# k02-breakout.net
KiCad netlist of a schematic drawn in Altium Designer
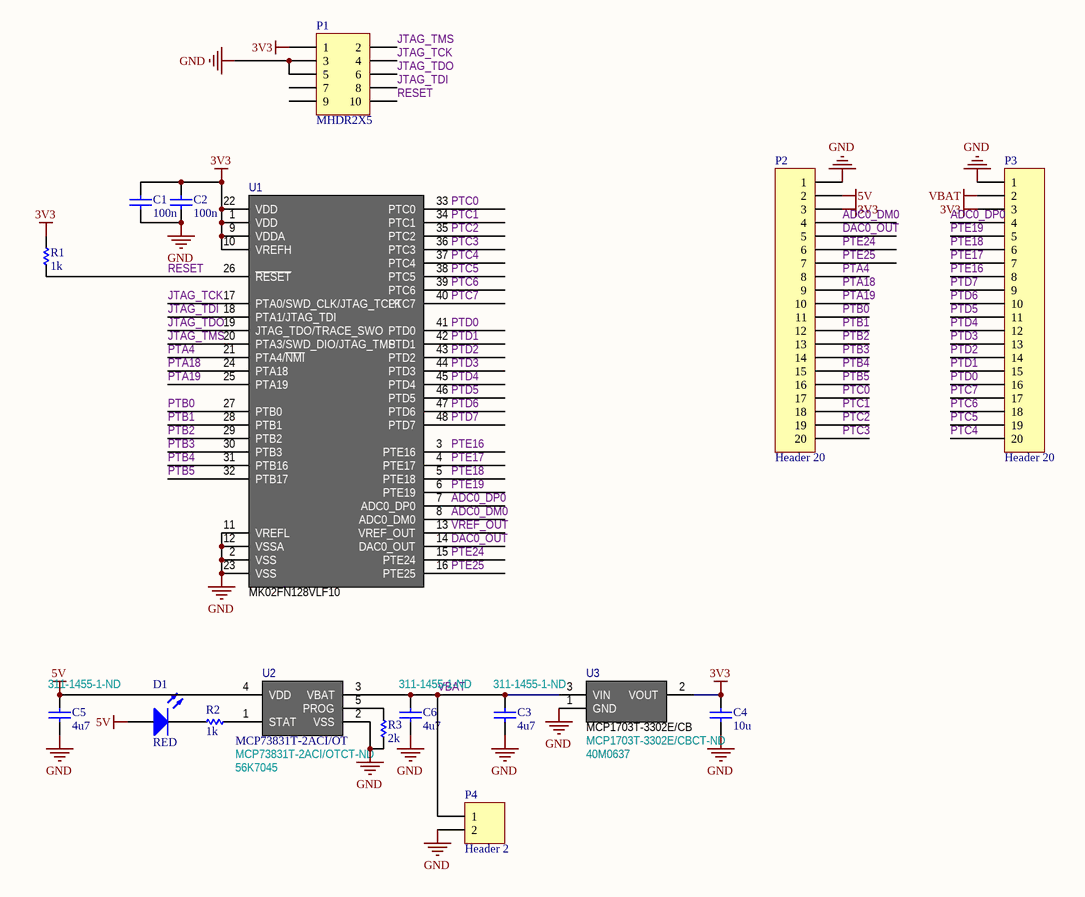
[diagram p0: k02-breakout.SchDoc]

(export (version "E")
  (design (tool "Eeschema 10.0.6"))
  (components
    (comp (ref "C1")
      (value "100n")
      (footprint "CAPC1608N")
      (description "Capacitor (Semiconductor SIM Model)")
      (fields (field (name "PUBLISHER") "Altium Limited"))
      (libsource (lib "Miscellaneous Devices") (part "Cap Semi"))
    )
    (comp (ref "C2")
      (value "100n")
      (footprint "CAPC1608N")
      (description "Capacitor (Semiconductor SIM Model)")
      (fields (field (name "PUBLISHER") "Altium Limited"))
      (libsource (lib "Miscellaneous Devices") (part "Cap Semi"))
    )
    (comp (ref "C3")
      (value "4u7")
      (footprint "CAPC1608N")
      (description "CAP SEMI 4U7 10V 0603")
      (fields
        (field (name "SUPPLIER PART NUMBER 1") "311-1455-1-ND")
        (field (name "PUBLISHER") "Altium Limited")
      )
      (libsource (lib "Miscellaneous Devices") (part "Cap Semi"))
    )
    (comp (ref "C4")
      (value "10u")
      (footprint "CAPC1608N")
      (description "Capacitor (Semiconductor SIM Model)")
      (fields (field (name "PUBLISHER") "Altium Limited"))
      (libsource (lib "Miscellaneous Devices") (part "Cap Semi"))
    )
    (comp (ref "C5")
      (value "4u7")
      (footprint "CAPC1608N")
      (description "CAP SEMI 4U7 10V 0603")
      (fields
        (field (name "SUPPLIER PART NUMBER 1") "311-1455-1-ND")
        (field (name "PUBLISHER") "Altium Limited")
      )
      (libsource (lib "Miscellaneous Devices") (part "Cap Semi"))
    )
    (comp (ref "C6")
      (value "4u7")
      (footprint "CAPC1608N")
      (description "CAP SEMI 4U7 10V 0603")
      (fields
        (field (name "SUPPLIER PART NUMBER 1") "311-1455-1-ND")
        (field (name "PUBLISHER") "Altium Limited")
      )
      (libsource (lib "Miscellaneous Devices") (part "Cap Semi"))
    )
    (comp (ref "D1")
      (value "RED")
      (footprint "LTST-C190EKT")
      (description "Typical greenGaAs LED")
      (fields (field (name "PUBLISHER") "Altium Limited"))
      (libsource (lib "Miscellaneous Devices") (part "LED_GREEN"))
    )
    (comp (ref "P1")
      (value "MHDR2X5")
      (footprint "MHDR2X5SMD")
      (description "Header, 5-Pin, Dual row")
      (fields (field (name "PUBLISHER") "Altium Limited"))
      (libsource (lib "Miscellaneous Connectors") (part "MHDR2X5"))
    )
    (comp (ref "P2")
      (value "Header 20")
      (footprint "HDR1X20")
      (description "Header, 20-Pin")
      (fields (field (name "PUBLISHER") "Altium Limited"))
      (libsource (lib "") (part "Header 20_1"))
    )
    (comp (ref "P3")
      (value "Header 20")
      (footprint "HDR1X20")
      (description "Header, 20-Pin")
      (fields (field (name "PUBLISHER") "Altium Limited"))
      (libsource (lib "Miscellaneous Connectors") (part "Header 20"))
    )
    (comp (ref "P4")
      (value "Header 2")
      (footprint "S2B-PH-SM4-TB")
      (description "Header, 2-Pin")
      (fields (field (name "PUBLISHER") "Altium Limited"))
      (libsource (lib "Miscellaneous Connectors") (part "Header 2"))
    )
    (comp (ref "R1")
      (value "1k")
      (footprint "RESC1608N")
      (description "Semiconductor Resistor")
      (fields (field (name "PUBLISHER") "Altium Limited"))
      (libsource (lib "Miscellaneous Devices") (part "Res Semi"))
    )
    (comp (ref "R2")
      (value "1k")
      (footprint "RESC1608N")
      (description "Semiconductor Resistor")
      (fields (field (name "PUBLISHER") "Altium Limited"))
      (libsource (lib "Miscellaneous Devices") (part "Res Semi"))
    )
    (comp (ref "R3")
      (value "2k")
      (footprint "RESC1608N")
      (description "Semiconductor Resistor")
      (fields (field (name "PUBLISHER") "Altium Limited"))
      (libsource (lib "Miscellaneous Devices") (part "Res Semi"))
    )
    (comp (ref "U1")
      (value "MK02FN128VLF10")
      (footprint "TSQFP50P900X900-48N")
      (description "IC MCU ARM 100MHz 128KB FLASH LQFP48")
      (libsource (lib "Freescale Kinetis ARM Microcontroller") (part "MK02FN128VLF10"))
    )
    (comp (ref "U2")
      (value "MCP73831T-2ACI/OT")
      (footprint "SOT23-5AN")
      (description "IC CONTROLLR LI-ION 4.2V SOT23-5")
      (fields
        (field (name "MANUFACTURER") "Microchip Technology")
        (field (name "SUPPLIER PART NUMBER 1") "MCP73831T-2ACI/OTCT-ND")
        (field (name "SUPPLIER PART NUMBER 2") "56K7045")
      )
      (libsource (lib "Microchip Battery Charger") (part "MCP73831T-2ACI/OT"))
    )
    (comp (ref "U3")
      (value "MCP1703T-3302E/CB")
      (footprint "SOT23-3N")
      (description "IC REG LDO 3.3V 0.25A SOT23A-3")
      (fields
        (field (name "MANUFACTURER") "Microchip Technology")
        (field (name "SUPPLIER PART NUMBER 1") "MCP1703T-3302E/CBCT-ND")
        (field (name "SUPPLIER PART NUMBER 2") "40M0637")
      )
      (libsource (lib "Microchip Linear Regulator") (part "MCP1703T-3302E/CB"))
    )
  )
  (nets
    (net (code "1") (name "/ADC0_DM0") (class "Default")
      (node (ref "P2") (pin "4") (pinfunction "4_4") (pintype "passive"))
      (node (ref "U1") (pin "8") (pinfunction "ADC0_DM0_8") (pintype "power_in"))
    )
    (net (code "2") (name "/ADC0_DP0") (class "Default")
      (node (ref "P3") (pin "4") (pinfunction "4_4") (pintype "passive"))
      (node (ref "U1") (pin "7") (pinfunction "ADC0_DP0_7") (pintype "power_in"))
    )
    (net (code "3") (name "/DAC0_OUT") (class "Default")
      (node (ref "P2") (pin "5") (pinfunction "5_5") (pintype "passive"))
      (node (ref "U1") (pin "14") (pinfunction "DAC0_OUT_14") (pintype "power_in"))
    )
    (net (code "4") (name "/JTAG_TCK") (class "Default")
      (node (ref "P1") (pin "4") (pinfunction "4_4") (pintype "passive"))
      (node (ref "U1") (pin "17") (pinfunction "PTA0/SWD_CLK/JTAG_TCLK_17") (pintype "power_in"))
    )
    (net (code "5") (name "/JTAG_TDI") (class "Default")
      (node (ref "P1") (pin "8") (pinfunction "8_8") (pintype "passive"))
      (node (ref "U1") (pin "18") (pinfunction "PTA1/JTAG_TDI_18") (pintype "power_in"))
    )
    (net (code "6") (name "/JTAG_TDO") (class "Default")
      (node (ref "P1") (pin "6") (pinfunction "6_6") (pintype "passive"))
      (node (ref "U1") (pin "19") (pinfunction "JTAG_TDO/TRACE_SWO_19") (pintype "power_in"))
    )
    (net (code "7") (name "/JTAG_TMS") (class "Default")
      (node (ref "P1") (pin "2") (pinfunction "2_2") (pintype "passive"))
      (node (ref "U1") (pin "20") (pinfunction "PTA3/SWD_DIO/JTAG_TMS_20") (pintype "power_in"))
    )
    (net (code "8") (name "/PTA4") (class "Default")
      (node (ref "P2") (pin "8") (pinfunction "8_8") (pintype "passive"))
      (node (ref "U1") (pin "21") (pinfunction "PTA4/~{NMI}_21") (pintype "power_in"))
    )
    (net (code "9") (name "/PTA18") (class "Default")
      (node (ref "P2") (pin "9") (pinfunction "9_9") (pintype "passive"))
      (node (ref "U1") (pin "24") (pinfunction "PTA18_24") (pintype "power_in"))
    )
    (net (code "10") (name "/PTA19") (class "Default")
      (node (ref "P2") (pin "10") (pinfunction "10_10") (pintype "passive"))
      (node (ref "U1") (pin "25") (pinfunction "PTA19_25") (pintype "power_in"))
    )
    (net (code "11") (name "/PTB0") (class "Default")
      (node (ref "P2") (pin "11") (pinfunction "11_11") (pintype "passive"))
      (node (ref "U1") (pin "27") (pinfunction "PTB0_27") (pintype "power_in"))
    )
    (net (code "12") (name "/PTB1") (class "Default")
      (node (ref "P2") (pin "12") (pinfunction "12_12") (pintype "passive"))
      (node (ref "U1") (pin "28") (pinfunction "PTB1_28") (pintype "power_in"))
    )
    (net (code "13") (name "/PTB2") (class "Default")
      (node (ref "P2") (pin "13") (pinfunction "13_13") (pintype "passive"))
      (node (ref "U1") (pin "29") (pinfunction "PTB2_29") (pintype "power_in"))
    )
    (net (code "14") (name "/PTB3") (class "Default")
      (node (ref "P2") (pin "14") (pinfunction "14_14") (pintype "passive"))
      (node (ref "U1") (pin "30") (pinfunction "PTB3_30") (pintype "power_in"))
    )
    (net (code "15") (name "/PTB4") (class "Default")
      (node (ref "P2") (pin "15") (pinfunction "15_15") (pintype "passive"))
      (node (ref "U1") (pin "31") (pinfunction "PTB16_31") (pintype "power_in"))
    )
    (net (code "16") (name "/PTB5") (class "Default")
      (node (ref "P2") (pin "16") (pinfunction "16_16") (pintype "passive"))
      (node (ref "U1") (pin "32") (pinfunction "PTB17_32") (pintype "power_in"))
    )
    (net (code "17") (name "/PTC0") (class "Default")
      (node (ref "P2") (pin "17") (pinfunction "17_17") (pintype "passive"))
      (node (ref "U1") (pin "33") (pinfunction "PTC0_33") (pintype "power_in"))
    )
    (net (code "18") (name "/PTC1") (class "Default")
      (node (ref "P2") (pin "18") (pinfunction "18_18") (pintype "passive"))
      (node (ref "U1") (pin "34") (pinfunction "PTC1_34") (pintype "power_in"))
    )
    (net (code "19") (name "/PTC2") (class "Default")
      (node (ref "P2") (pin "19") (pinfunction "19_19") (pintype "passive"))
      (node (ref "U1") (pin "35") (pinfunction "PTC2_35") (pintype "power_in"))
    )
    (net (code "20") (name "/PTC3") (class "Default")
      (node (ref "P2") (pin "20") (pinfunction "20_20") (pintype "passive"))
      (node (ref "U1") (pin "36") (pinfunction "PTC3_36") (pintype "power_in"))
    )
    (net (code "21") (name "/PTC4") (class "Default")
      (node (ref "P3") (pin "20") (pinfunction "20_20") (pintype "passive"))
      (node (ref "U1") (pin "37") (pinfunction "PTC4_37") (pintype "power_in"))
    )
    (net (code "22") (name "/PTC5") (class "Default")
      (node (ref "P3") (pin "19") (pinfunction "19_19") (pintype "passive"))
      (node (ref "U1") (pin "38") (pinfunction "PTC5_38") (pintype "power_in"))
    )
    (net (code "23") (name "/PTC6") (class "Default")
      (node (ref "P3") (pin "18") (pinfunction "18_18") (pintype "passive"))
      (node (ref "U1") (pin "39") (pinfunction "PTC6_39") (pintype "power_in"))
    )
    (net (code "24") (name "/PTC7") (class "Default")
      (node (ref "P3") (pin "17") (pinfunction "17_17") (pintype "passive"))
      (node (ref "U1") (pin "40") (pinfunction "PTC7_40") (pintype "power_in"))
    )
    (net (code "25") (name "/PTD0") (class "Default")
      (node (ref "P3") (pin "16") (pinfunction "16_16") (pintype "passive"))
      (node (ref "U1") (pin "41") (pinfunction "PTD0_41") (pintype "power_in"))
    )
    (net (code "26") (name "/PTD1") (class "Default")
      (node (ref "P3") (pin "15") (pinfunction "15_15") (pintype "passive"))
      (node (ref "U1") (pin "42") (pinfunction "PTD1_42") (pintype "power_in"))
    )
    (net (code "27") (name "/PTD2") (class "Default")
      (node (ref "P3") (pin "14") (pinfunction "14_14") (pintype "passive"))
      (node (ref "U1") (pin "43") (pinfunction "PTD2_43") (pintype "power_in"))
    )
    (net (code "28") (name "/PTD3") (class "Default")
      (node (ref "P3") (pin "13") (pinfunction "13_13") (pintype "passive"))
      (node (ref "U1") (pin "44") (pinfunction "PTD3_44") (pintype "power_in"))
    )
    (net (code "29") (name "/PTD4") (class "Default")
      (node (ref "P3") (pin "12") (pinfunction "12_12") (pintype "passive"))
      (node (ref "U1") (pin "45") (pinfunction "PTD4_45") (pintype "power_in"))
    )
    (net (code "30") (name "/PTD5") (class "Default")
      (node (ref "P3") (pin "11") (pinfunction "11_11") (pintype "passive"))
      (node (ref "U1") (pin "46") (pinfunction "PTD5_46") (pintype "power_in"))
    )
    (net (code "31") (name "/PTD6") (class "Default")
      (node (ref "P3") (pin "10") (pinfunction "10_10") (pintype "passive"))
      (node (ref "U1") (pin "47") (pinfunction "PTD6_47") (pintype "power_in"))
    )
    (net (code "32") (name "/PTD7") (class "Default")
      (node (ref "P3") (pin "9") (pinfunction "9_9") (pintype "passive"))
      (node (ref "U1") (pin "48") (pinfunction "PTD7_48") (pintype "power_in"))
    )
    (net (code "33") (name "/PTE16") (class "Default")
      (node (ref "P3") (pin "8") (pinfunction "8_8") (pintype "passive"))
      (node (ref "U1") (pin "3") (pinfunction "PTE16_3") (pintype "power_in"))
    )
    (net (code "34") (name "/PTE17") (class "Default")
      (node (ref "P3") (pin "7") (pinfunction "7_7") (pintype "passive"))
      (node (ref "U1") (pin "4") (pinfunction "PTE17_4") (pintype "power_in"))
    )
    (net (code "35") (name "/PTE18") (class "Default")
      (node (ref "P3") (pin "6") (pinfunction "6_6") (pintype "passive"))
      (node (ref "U1") (pin "5") (pinfunction "PTE18_5") (pintype "power_in"))
    )
    (net (code "36") (name "/PTE19") (class "Default")
      (node (ref "P3") (pin "5") (pinfunction "5_5") (pintype "passive"))
      (node (ref "U1") (pin "6") (pinfunction "PTE19_6") (pintype "power_in"))
    )
    (net (code "37") (name "/PTE24") (class "Default")
      (node (ref "P2") (pin "6") (pinfunction "6_6") (pintype "passive"))
      (node (ref "U1") (pin "15") (pinfunction "PTE24_15") (pintype "power_in"))
    )
    (net (code "38") (name "/PTE25") (class "Default")
      (node (ref "P2") (pin "7") (pinfunction "7_7") (pintype "passive"))
      (node (ref "U1") (pin "16") (pinfunction "PTE25_16") (pintype "power_in"))
    )
    (net (code "39") (name "/RESET") (class "Default")
      (node (ref "P1") (pin "10") (pinfunction "10_10") (pintype "passive"))
      (node (ref "R1") (pin "1") (pinfunction "1_1") (pintype "passive"))
      (node (ref "U1") (pin "26") (pinfunction "~{RESET}_26") (pintype "power_in"))
    )
    (net (code "40") (name "/VREF_OUT") (class "Default")
      (node (ref "U1") (pin "13") (pinfunction "VREF_OUT_13") (pintype "power_in"))
    )
    (net (code "41") (name "3V3") (class "Default")
      (node (ref "C1") (pin "2") (pinfunction "2_2") (pintype "passive"))
      (node (ref "C2") (pin "2") (pinfunction "2_2") (pintype "passive"))
      (node (ref "C4") (pin "2") (pinfunction "2_2") (pintype "passive"))
      (node (ref "P1") (pin "1") (pinfunction "1_1") (pintype "passive"))
      (node (ref "P2") (pin "3") (pinfunction "3_3") (pintype "passive"))
      (node (ref "P3") (pin "3") (pinfunction "3_3") (pintype "passive"))
      (node (ref "R1") (pin "2") (pinfunction "2_2") (pintype "passive"))
      (node (ref "U1") (pin "1") (pinfunction "VDD_1") (pintype "power_in"))
      (node (ref "U1") (pin "10") (pinfunction "VREFH_10") (pintype "power_in"))
      (node (ref "U1") (pin "22") (pinfunction "VDD_22") (pintype "power_in"))
      (node (ref "U1") (pin "9") (pinfunction "VDDA_9") (pintype "power_in"))
      (node (ref "U3") (pin "2") (pinfunction "VOUT_2") (pintype "power_in"))
    )
    (net (code "42") (name "5V") (class "Default")
      (node (ref "C5") (pin "2") (pinfunction "2_2") (pintype "passive"))
      (node (ref "D1") (pin "1") (pinfunction "A_1") (pintype "passive"))
      (node (ref "P2") (pin "2") (pinfunction "2_2") (pintype "passive"))
      (node (ref "U2") (pin "4") (pinfunction "VDD_4") (pintype "power_in"))
    )
    (net (code "43") (name "GND") (class "Default")
      (node (ref "C1") (pin "1") (pinfunction "1_1") (pintype "passive"))
      (node (ref "C2") (pin "1") (pinfunction "1_1") (pintype "passive"))
      (node (ref "C3") (pin "1") (pinfunction "1_1") (pintype "passive"))
      (node (ref "C4") (pin "1") (pinfunction "1_1") (pintype "passive"))
      (node (ref "C5") (pin "1") (pinfunction "1_1") (pintype "passive"))
      (node (ref "C6") (pin "1") (pinfunction "1_1") (pintype "passive"))
      (node (ref "P1") (pin "3") (pinfunction "3_3") (pintype "passive"))
      (node (ref "P1") (pin "5") (pinfunction "5_5") (pintype "passive"))
      (node (ref "P2") (pin "1") (pinfunction "1_1") (pintype "passive"))
      (node (ref "P3") (pin "1") (pinfunction "1_1") (pintype "passive"))
      (node (ref "P4") (pin "2") (pinfunction "2_2") (pintype "passive"))
      (node (ref "R3") (pin "1") (pinfunction "1_1") (pintype "passive"))
      (node (ref "U1") (pin "11") (pinfunction "VREFL_11") (pintype "power_in"))
      (node (ref "U1") (pin "12") (pinfunction "VSSA_12") (pintype "power_in"))
      (node (ref "U1") (pin "2") (pinfunction "VSS_2") (pintype "power_in"))
      (node (ref "U1") (pin "23") (pinfunction "VSS_23") (pintype "power_in"))
      (node (ref "U2") (pin "2") (pinfunction "VSS_2") (pintype "power_in"))
      (node (ref "U3") (pin "1") (pinfunction "GND_1") (pintype "power_in"))
    )
    (net (code "44") (name "Net-(D1-K)") (class "Default")
      (node (ref "D1") (pin "2") (pinfunction "K_2") (pintype "passive"))
      (node (ref "R2") (pin "2") (pinfunction "2_2") (pintype "passive"))
    )
    (net (code "45") (name "Net-(U2-PROG)") (class "Default")
      (node (ref "R3") (pin "2") (pinfunction "2_2") (pintype "passive"))
      (node (ref "U2") (pin "5") (pinfunction "PROG_5") (pintype "power_in"))
    )
    (net (code "46") (name "Net-(U2-STAT)") (class "Default")
      (node (ref "R2") (pin "1") (pinfunction "1_1") (pintype "passive"))
      (node (ref "U2") (pin "1") (pinfunction "STAT_1") (pintype "power_in"))
    )
    (net (code "47") (name "VBAT") (class "Default")
      (node (ref "C3") (pin "2") (pinfunction "2_2") (pintype "passive"))
      (node (ref "C6") (pin "2") (pinfunction "2_2") (pintype "passive"))
      (node (ref "P3") (pin "2") (pinfunction "2_2") (pintype "passive"))
      (node (ref "P4") (pin "1") (pinfunction "1_1") (pintype "passive"))
      (node (ref "U2") (pin "3") (pinfunction "VBAT_3") (pintype "power_in"))
      (node (ref "U3") (pin "3") (pinfunction "VIN_3") (pintype "power_in"))
    )
    (net (code "48") (name "unconnected-(P1-Pad7)") (class "Default")
      (node (ref "P1") (pin "7") (pinfunction "7_7") (pintype "passive"))
    )
    (net (code "49") (name "unconnected-(P1-Pad9)") (class "Default")
      (node (ref "P1") (pin "9") (pinfunction "9_9") (pintype "passive"))
    )
  )
)
